# regsimple2addfp.net
KiCad netlist of a schematic drawn in EAGLE
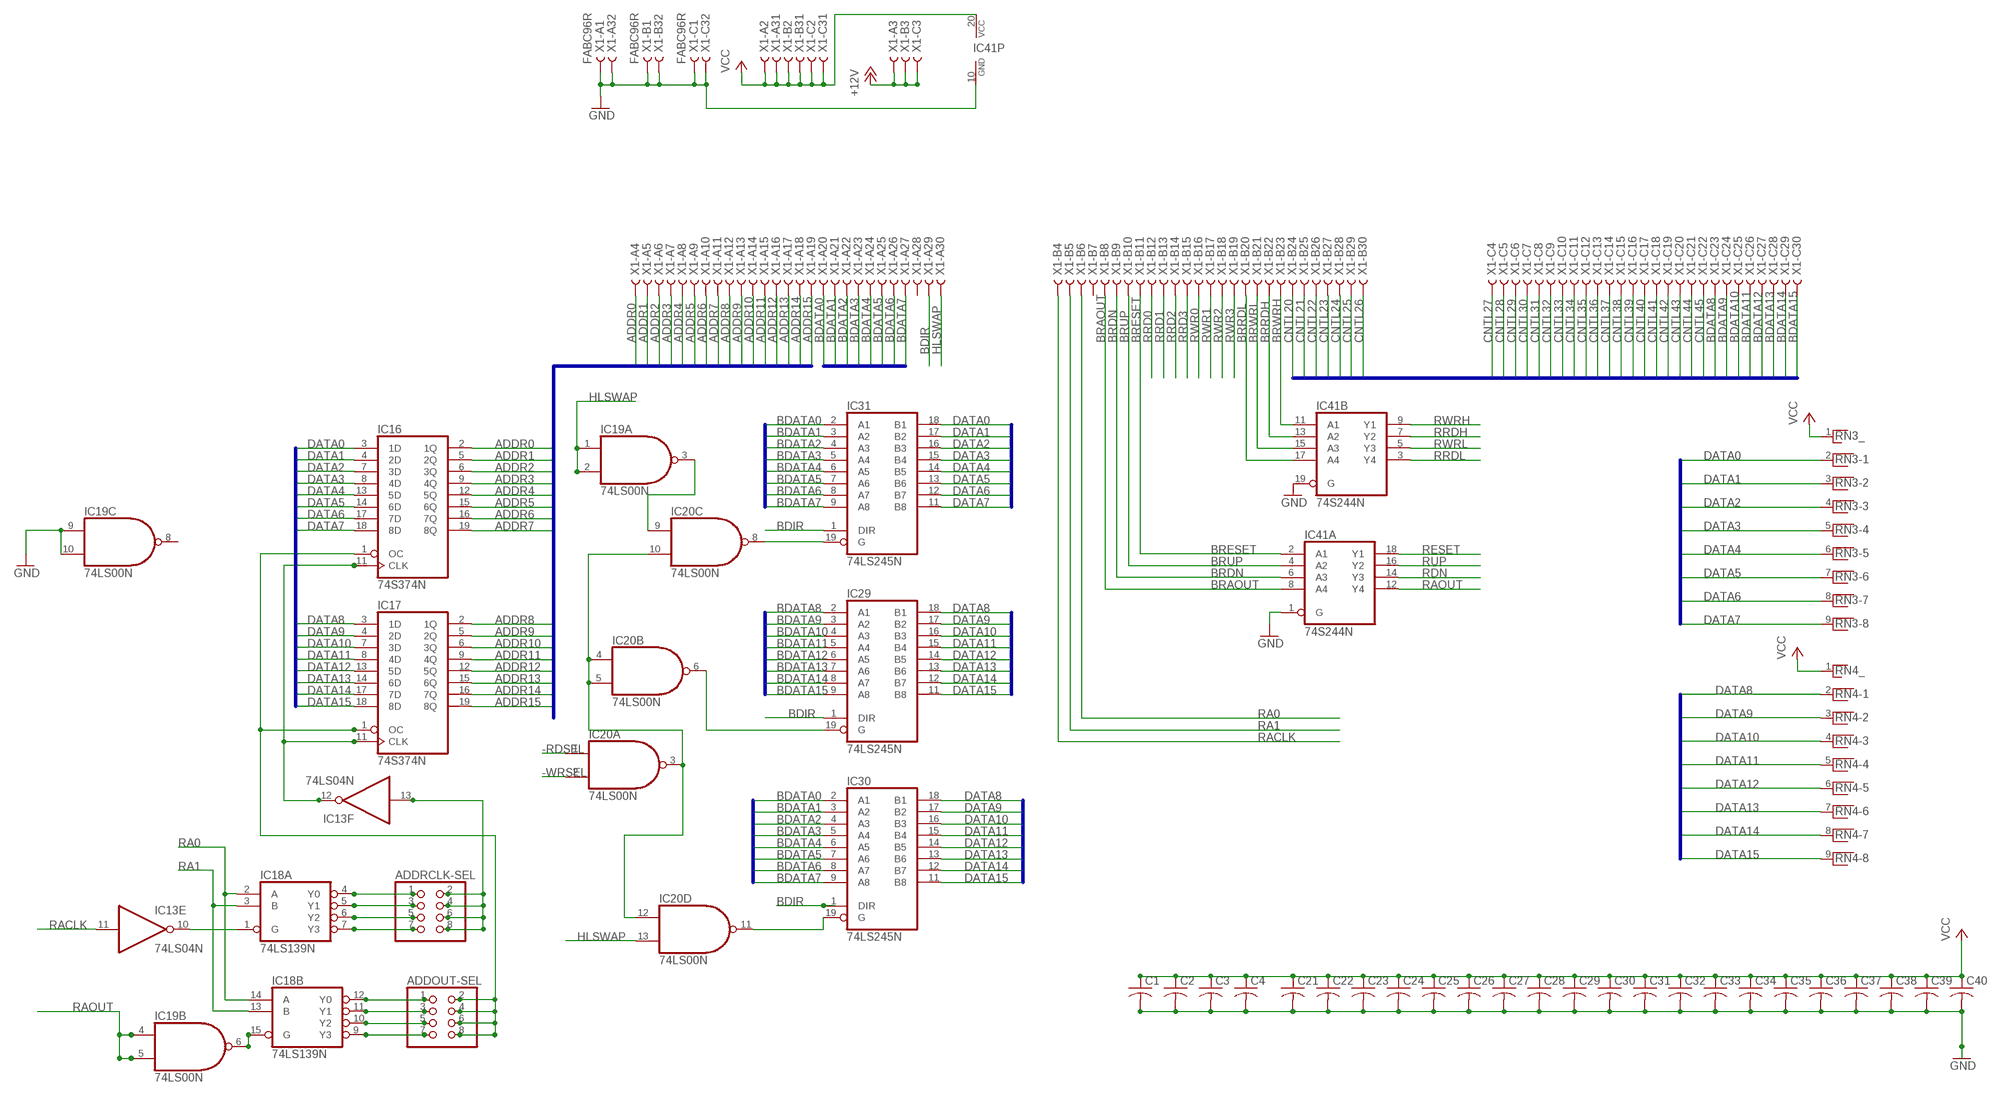
[diagram p0: schematic, sheet 1]
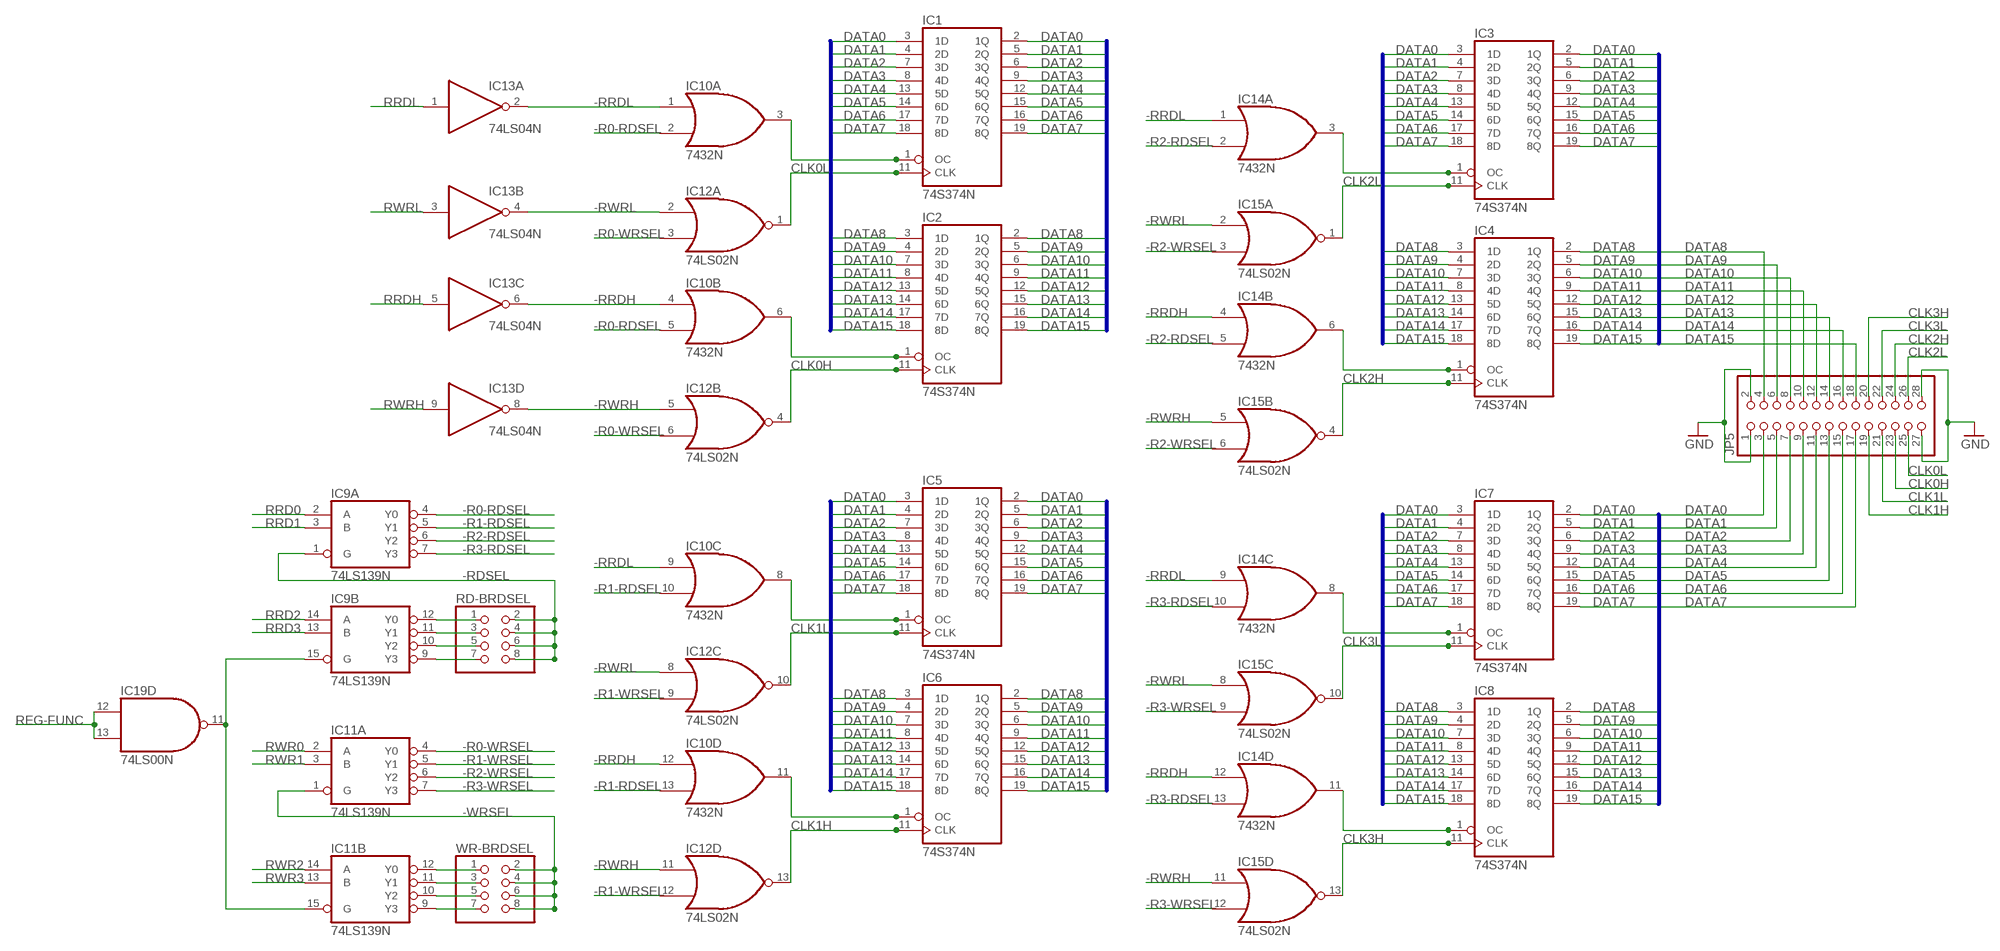
[diagram p1: schematic, sheet 2]

(export (version "E")
  (design (tool "Eeschema 10.0.6"))
  (components
    (comp (ref "IC1")
      (value "74S374N")
      (footprint "eagle-import:DIL20")
      (libsource (lib "eagle-import") (part "74374NS"))
    )
    (comp (ref "IC2")
      (value "74S374N")
      (footprint "eagle-import:DIL20")
      (libsource (lib "eagle-import") (part "74374NS"))
    )
    (comp (ref "IC3")
      (value "74S374N")
      (footprint "eagle-import:DIL20")
      (libsource (lib "eagle-import") (part "74374NS"))
    )
    (comp (ref "IC4")
      (value "74S374N")
      (footprint "eagle-import:DIL20")
      (libsource (lib "eagle-import") (part "74374NS"))
    )
    (comp (ref "IC5")
      (value "74S374N")
      (footprint "eagle-import:DIL20")
      (libsource (lib "eagle-import") (part "74374NS"))
    )
    (comp (ref "IC6")
      (value "74S374N")
      (footprint "eagle-import:DIL20")
      (libsource (lib "eagle-import") (part "74374NS"))
    )
    (comp (ref "IC7")
      (value "74S374N")
      (footprint "eagle-import:DIL20")
      (libsource (lib "eagle-import") (part "74374NS"))
    )
    (comp (ref "IC8")
      (value "74S374N")
      (footprint "eagle-import:DIL20")
      (libsource (lib "eagle-import") (part "74374NS"))
    )
    (comp (ref "IC9")
      (value "74LS139N")
      (footprint "eagle-import:DIL16")
      (libsource (lib "eagle-import") (part "74139NLS"))
    )
    (comp (ref "IC10")
      (value "7432N")
      (footprint "eagle-import:DIL14")
      (libsource (lib "eagle-import") (part "7432N"))
    )
    (comp (ref "IC11")
      (value "74LS139N")
      (footprint "eagle-import:DIL16")
      (libsource (lib "eagle-import") (part "74139NLS"))
    )
    (comp (ref "IC12")
      (value "74LS02N")
      (footprint "eagle-import:DIL14")
      (libsource (lib "eagle-import") (part "7402NLS"))
    )
    (comp (ref "IC13")
      (value "74LS04N")
      (footprint "eagle-import:DIL14")
      (libsource (lib "eagle-import") (part "7404NLS"))
    )
    (comp (ref "IC14")
      (value "7432N")
      (footprint "eagle-import:DIL14")
      (libsource (lib "eagle-import") (part "7432N"))
    )
    (comp (ref "IC15")
      (value "74LS02N")
      (footprint "eagle-import:DIL14")
      (libsource (lib "eagle-import") (part "7402NLS"))
    )
    (comp (ref "IC19")
      (value "74LS00N")
      (footprint "eagle-import:DIL14")
      (libsource (lib "eagle-import") (part "7400NLS"))
    )
    (comp (ref "JP5")
      (value "PINHD-2X14")
      (footprint "eagle-import:2X14")
      (libsource (lib "eagle-import") (part "PINHD-2X14"))
    )
    (comp (ref "RD-BRDSEL")
      (value "PINHD-2X4")
      (footprint "eagle-import:2X04")
      (libsource (lib "eagle-import") (part "PINHD-2X4"))
    )
    (comp (ref "WR-BRDSEL")
      (value "PINHD-2X4")
      (footprint "eagle-import:2X04")
      (libsource (lib "eagle-import") (part "PINHD-2X4"))
    )
    (comp (ref "ADDOUT-SEL")
      (value "PINHD-2X4")
      (footprint "eagle-import:2X04")
      (libsource (lib "eagle-import") (part "PINHD-2X4"))
    )
    (comp (ref "ADDRCLK-SEL")
      (value "PINHD-2X4")
      (footprint "eagle-import:2X04")
      (libsource (lib "eagle-import") (part "PINHD-2X4"))
    )
    (comp (ref "C1")
      (value "C-US025-040X050")
      (footprint "eagle-import:C025-040X050")
      (libsource (lib "eagle-import") (part "C-US025-040X050"))
    )
    (comp (ref "C2")
      (value "C-US025-040X050")
      (footprint "eagle-import:C025-040X050")
      (libsource (lib "eagle-import") (part "C-US025-040X050"))
    )
    (comp (ref "C3")
      (value "C-US025-040X050")
      (footprint "eagle-import:C025-040X050")
      (libsource (lib "eagle-import") (part "C-US025-040X050"))
    )
    (comp (ref "C4")
      (value "C-US025-040X050")
      (footprint "eagle-import:C025-040X050")
      (libsource (lib "eagle-import") (part "C-US025-040X050"))
    )
    (comp (ref "C21")
      (value "C-US025-040X050")
      (footprint "eagle-import:C025-040X050")
      (libsource (lib "eagle-import") (part "C-US025-040X050"))
    )
    (comp (ref "C22")
      (value "C-US025-040X050")
      (footprint "eagle-import:C025-040X050")
      (libsource (lib "eagle-import") (part "C-US025-040X050"))
    )
    (comp (ref "C23")
      (value "C-US025-040X050")
      (footprint "eagle-import:C025-040X050")
      (libsource (lib "eagle-import") (part "C-US025-040X050"))
    )
    (comp (ref "C24")
      (value "C-US025-040X050")
      (footprint "eagle-import:C025-040X050")
      (libsource (lib "eagle-import") (part "C-US025-040X050"))
    )
    (comp (ref "C25")
      (value "C-US025-040X050")
      (footprint "eagle-import:C025-040X050")
      (libsource (lib "eagle-import") (part "C-US025-040X050"))
    )
    (comp (ref "C26")
      (value "C-US025-040X050")
      (footprint "eagle-import:C025-040X050")
      (libsource (lib "eagle-import") (part "C-US025-040X050"))
    )
    (comp (ref "C27")
      (value "C-US025-040X050")
      (footprint "eagle-import:C025-040X050")
      (libsource (lib "eagle-import") (part "C-US025-040X050"))
    )
    (comp (ref "C28")
      (value "C-US025-040X050")
      (footprint "eagle-import:C025-040X050")
      (libsource (lib "eagle-import") (part "C-US025-040X050"))
    )
    (comp (ref "C29")
      (value "C-US025-040X050")
      (footprint "eagle-import:C025-040X050")
      (libsource (lib "eagle-import") (part "C-US025-040X050"))
    )
    (comp (ref "C30")
      (value "C-US025-040X050")
      (footprint "eagle-import:C025-040X050")
      (libsource (lib "eagle-import") (part "C-US025-040X050"))
    )
    (comp (ref "C31")
      (value "C-US025-040X050")
      (footprint "eagle-import:C025-040X050")
      (libsource (lib "eagle-import") (part "C-US025-040X050"))
    )
    (comp (ref "C32")
      (value "C-US025-040X050")
      (footprint "eagle-import:C025-040X050")
      (libsource (lib "eagle-import") (part "C-US025-040X050"))
    )
    (comp (ref "C33")
      (value "C-US025-040X050")
      (footprint "eagle-import:C025-040X050")
      (libsource (lib "eagle-import") (part "C-US025-040X050"))
    )
    (comp (ref "C34")
      (value "C-US025-040X050")
      (footprint "eagle-import:C025-040X050")
      (libsource (lib "eagle-import") (part "C-US025-040X050"))
    )
    (comp (ref "C35")
      (value "C-US025-040X050")
      (footprint "eagle-import:C025-040X050")
      (libsource (lib "eagle-import") (part "C-US025-040X050"))
    )
    (comp (ref "C36")
      (value "C-US025-040X050")
      (footprint "eagle-import:C025-040X050")
      (libsource (lib "eagle-import") (part "C-US025-040X050"))
    )
    (comp (ref "C37")
      (value "C-US025-040X050")
      (footprint "eagle-import:C025-040X050")
      (libsource (lib "eagle-import") (part "C-US025-040X050"))
    )
    (comp (ref "C38")
      (value "C-US025-040X050")
      (footprint "eagle-import:C025-040X050")
      (libsource (lib "eagle-import") (part "C-US025-040X050"))
    )
    (comp (ref "C39")
      (value "C-US025-040X050")
      (footprint "eagle-import:C025-040X050")
      (libsource (lib "eagle-import") (part "C-US025-040X050"))
    )
    (comp (ref "C40")
      (value "C-US025-040X050")
      (footprint "eagle-import:C025-040X050")
      (libsource (lib "eagle-import") (part "C-US025-040X050"))
    )
    (comp (ref "IC16")
      (value "74S374N")
      (footprint "eagle-import:DIL20")
      (libsource (lib "eagle-import") (part "74374NS"))
    )
    (comp (ref "IC17")
      (value "74S374N")
      (footprint "eagle-import:DIL20")
      (libsource (lib "eagle-import") (part "74374NS"))
    )
    (comp (ref "IC18")
      (value "74LS139N")
      (footprint "eagle-import:DIL16")
      (libsource (lib "eagle-import") (part "74139NLS"))
    )
    (comp (ref "IC20")
      (value "74LS00N")
      (footprint "eagle-import:DIL14")
      (libsource (lib "eagle-import") (part "7400NLS"))
    )
    (comp (ref "IC29")
      (value "74LS245N")
      (footprint "eagle-import:DIL20")
      (libsource (lib "eagle-import") (part "74245NLS"))
    )
    (comp (ref "IC30")
      (value "74LS245N")
      (footprint "eagle-import:DIL20")
      (libsource (lib "eagle-import") (part "74245NLS"))
    )
    (comp (ref "IC31")
      (value "74LS245N")
      (footprint "eagle-import:DIL20")
      (libsource (lib "eagle-import") (part "74245NLS"))
    )
    (comp (ref "IC41")
      (value "74S244N")
      (footprint "eagle-import:DIL20")
      (libsource (lib "eagle-import") (part "74244NS"))
    )
    (comp (ref "RN3")
      (value "RNX8")
      (footprint "eagle-import:RN-9")
      (libsource (lib "eagle-import") (part "RNX8"))
    )
    (comp (ref "RN4")
      (value "RNX8")
      (footprint "eagle-import:RN-9")
      (libsource (lib "eagle-import") (part "RNX8"))
    )
    (comp (ref "X1")
      (value "FABC96R")
      (footprint "eagle-import:FABC96R")
      (libsource (lib "eagle-import") (part "FABC96R"))
    )
  )
  (nets
    (net (code "1") (name "+12V") (class "Default")
      (node (ref "X1") (pin "A3") (pinfunction "B_A3") (pintype "passive"))
      (node (ref "X1") (pin "B3") (pinfunction "B_B3") (pintype "passive"))
      (node (ref "X1") (pin "C3") (pinfunction "B_C3") (pintype "passive"))
    )
    (net (code "2") (name "-R0-RDSEL") (class "Default")
      (node (ref "IC10") (pin "2") (pinfunction "I1_2") (pintype "input"))
      (node (ref "IC10") (pin "5") (pinfunction "I1_5") (pintype "input"))
      (node (ref "IC9") (pin "4") (pinfunction "Y0_4") (pintype "output"))
    )
    (net (code "3") (name "-R0-WRSEL") (class "Default")
      (node (ref "IC11") (pin "4") (pinfunction "Y0_4") (pintype "output"))
      (node (ref "IC12") (pin "3") (pinfunction "I1_3") (pintype "input"))
      (node (ref "IC12") (pin "6") (pinfunction "I1_6") (pintype "input"))
    )
    (net (code "4") (name "-R1-RDSEL") (class "Default")
      (node (ref "IC10") (pin "10") (pinfunction "I1_10") (pintype "input"))
      (node (ref "IC10") (pin "13") (pinfunction "I1_13") (pintype "input"))
      (node (ref "IC9") (pin "5") (pinfunction "Y1_5") (pintype "output"))
    )
    (net (code "5") (name "-R1-WRSEL") (class "Default")
      (node (ref "IC11") (pin "5") (pinfunction "Y1_5") (pintype "output"))
      (node (ref "IC12") (pin "12") (pinfunction "I1_12") (pintype "input"))
      (node (ref "IC12") (pin "9") (pinfunction "I1_9") (pintype "input"))
    )
    (net (code "6") (name "-R2-RDSEL") (class "Default")
      (node (ref "IC14") (pin "2") (pinfunction "I1_2") (pintype "input"))
      (node (ref "IC14") (pin "5") (pinfunction "I1_5") (pintype "input"))
      (node (ref "IC9") (pin "6") (pinfunction "Y2_6") (pintype "output"))
    )
    (net (code "7") (name "-R2-WRSEL") (class "Default")
      (node (ref "IC11") (pin "6") (pinfunction "Y2_6") (pintype "output"))
      (node (ref "IC15") (pin "3") (pinfunction "I1_3") (pintype "input"))
      (node (ref "IC15") (pin "6") (pinfunction "I1_6") (pintype "input"))
    )
    (net (code "8") (name "-R3-RDSEL") (class "Default")
      (node (ref "IC14") (pin "10") (pinfunction "I1_10") (pintype "input"))
      (node (ref "IC14") (pin "13") (pinfunction "I1_13") (pintype "input"))
      (node (ref "IC9") (pin "7") (pinfunction "Y3_7") (pintype "output"))
    )
    (net (code "9") (name "-R3-WRSEL") (class "Default")
      (node (ref "IC11") (pin "7") (pinfunction "Y3_7") (pintype "output"))
      (node (ref "IC15") (pin "12") (pinfunction "I1_12") (pintype "input"))
      (node (ref "IC15") (pin "9") (pinfunction "I1_9") (pintype "input"))
    )
    (net (code "10") (name "-RDSEL") (class "Default")
      (node (ref "IC20") (pin "1") (pinfunction "I0_1") (pintype "input"))
      (node (ref "IC9") (pin "1") (pinfunction "G_1") (pintype "input"))
      (node (ref "RD-BRDSEL") (pin "2") (pinfunction "2_2") (pintype "passive"))
      (node (ref "RD-BRDSEL") (pin "4") (pinfunction "4_4") (pintype "passive"))
      (node (ref "RD-BRDSEL") (pin "6") (pinfunction "6_6") (pintype "passive"))
      (node (ref "RD-BRDSEL") (pin "8") (pinfunction "8_8") (pintype "passive"))
    )
    (net (code "11") (name "-RRDH") (class "Default")
      (node (ref "IC10") (pin "12") (pinfunction "I0_12") (pintype "input"))
      (node (ref "IC10") (pin "4") (pinfunction "I0_4") (pintype "input"))
      (node (ref "IC13") (pin "6") (pinfunction "O_6") (pintype "output"))
      (node (ref "IC14") (pin "12") (pinfunction "I0_12") (pintype "input"))
      (node (ref "IC14") (pin "4") (pinfunction "I0_4") (pintype "input"))
    )
    (net (code "12") (name "-RRDL") (class "Default")
      (node (ref "IC10") (pin "1") (pinfunction "I0_1") (pintype "input"))
      (node (ref "IC10") (pin "9") (pinfunction "I0_9") (pintype "input"))
      (node (ref "IC13") (pin "2") (pinfunction "O_2") (pintype "output"))
      (node (ref "IC14") (pin "1") (pinfunction "I0_1") (pintype "input"))
      (node (ref "IC14") (pin "9") (pinfunction "I0_9") (pintype "input"))
    )
    (net (code "13") (name "-RWRH") (class "Default")
      (node (ref "IC12") (pin "11") (pinfunction "I0_11") (pintype "input"))
      (node (ref "IC12") (pin "5") (pinfunction "I0_5") (pintype "input"))
      (node (ref "IC13") (pin "8") (pinfunction "O_8") (pintype "output"))
      (node (ref "IC15") (pin "11") (pinfunction "I0_11") (pintype "input"))
      (node (ref "IC15") (pin "5") (pinfunction "I0_5") (pintype "input"))
    )
    (net (code "14") (name "-RWRL") (class "Default")
      (node (ref "IC12") (pin "2") (pinfunction "I0_2") (pintype "input"))
      (node (ref "IC12") (pin "8") (pinfunction "I0_8") (pintype "input"))
      (node (ref "IC13") (pin "4") (pinfunction "O_4") (pintype "output"))
      (node (ref "IC15") (pin "2") (pinfunction "I0_2") (pintype "input"))
      (node (ref "IC15") (pin "8") (pinfunction "I0_8") (pintype "input"))
    )
    (net (code "15") (name "-WRSEL") (class "Default")
      (node (ref "IC11") (pin "1") (pinfunction "G_1") (pintype "input"))
      (node (ref "IC20") (pin "2") (pinfunction "I1_2") (pintype "input"))
      (node (ref "WR-BRDSEL") (pin "2") (pinfunction "2_2") (pintype "passive"))
      (node (ref "WR-BRDSEL") (pin "4") (pinfunction "4_4") (pintype "passive"))
      (node (ref "WR-BRDSEL") (pin "6") (pinfunction "6_6") (pintype "passive"))
      (node (ref "WR-BRDSEL") (pin "8") (pinfunction "8_8") (pintype "passive"))
    )
    (net (code "16") (name "ADDR0") (class "Default")
      (node (ref "IC16") (pin "2") (pinfunction "1Q_2") (pintype "tri_state"))
      (node (ref "X1") (pin "A4") (pinfunction "B_A4") (pintype "passive"))
    )
    (net (code "17") (name "ADDR1") (class "Default")
      (node (ref "IC16") (pin "5") (pinfunction "2Q_5") (pintype "tri_state"))
      (node (ref "X1") (pin "A5") (pinfunction "B_A5") (pintype "passive"))
    )
    (net (code "18") (name "ADDR2") (class "Default")
      (node (ref "IC16") (pin "6") (pinfunction "3Q_6") (pintype "tri_state"))
      (node (ref "X1") (pin "A6") (pinfunction "B_A6") (pintype "passive"))
    )
    (net (code "19") (name "ADDR3") (class "Default")
      (node (ref "IC16") (pin "9") (pinfunction "4Q_9") (pintype "tri_state"))
      (node (ref "X1") (pin "A7") (pinfunction "B_A7") (pintype "passive"))
    )
    (net (code "20") (name "ADDR4") (class "Default")
      (node (ref "IC16") (pin "12") (pinfunction "5Q_12") (pintype "tri_state"))
      (node (ref "X1") (pin "A8") (pinfunction "B_A8") (pintype "passive"))
    )
    (net (code "21") (name "ADDR5") (class "Default")
      (node (ref "IC16") (pin "15") (pinfunction "6Q_15") (pintype "tri_state"))
      (node (ref "X1") (pin "A9") (pinfunction "B_A9") (pintype "passive"))
    )
    (net (code "22") (name "ADDR6") (class "Default")
      (node (ref "IC16") (pin "16") (pinfunction "7Q_16") (pintype "tri_state"))
      (node (ref "X1") (pin "A10") (pinfunction "B_A10") (pintype "passive"))
    )
    (net (code "23") (name "ADDR7") (class "Default")
      (node (ref "IC16") (pin "19") (pinfunction "8Q_19") (pintype "tri_state"))
      (node (ref "X1") (pin "A11") (pinfunction "B_A11") (pintype "passive"))
    )
    (net (code "24") (name "ADDR8") (class "Default")
      (node (ref "IC17") (pin "2") (pinfunction "1Q_2") (pintype "tri_state"))
      (node (ref "X1") (pin "A12") (pinfunction "B_A12") (pintype "passive"))
    )
    (net (code "25") (name "ADDR9") (class "Default")
      (node (ref "IC17") (pin "5") (pinfunction "2Q_5") (pintype "tri_state"))
      (node (ref "X1") (pin "A13") (pinfunction "B_A13") (pintype "passive"))
    )
    (net (code "26") (name "ADDR10") (class "Default")
      (node (ref "IC17") (pin "6") (pinfunction "3Q_6") (pintype "tri_state"))
      (node (ref "X1") (pin "A14") (pinfunction "B_A14") (pintype "passive"))
    )
    (net (code "27") (name "ADDR11") (class "Default")
      (node (ref "IC17") (pin "9") (pinfunction "4Q_9") (pintype "tri_state"))
      (node (ref "X1") (pin "A15") (pinfunction "B_A15") (pintype "passive"))
    )
    (net (code "28") (name "ADDR12") (class "Default")
      (node (ref "IC17") (pin "12") (pinfunction "5Q_12") (pintype "tri_state"))
      (node (ref "X1") (pin "A16") (pinfunction "B_A16") (pintype "passive"))
    )
    (net (code "29") (name "ADDR13") (class "Default")
      (node (ref "IC17") (pin "15") (pinfunction "6Q_15") (pintype "tri_state"))
      (node (ref "X1") (pin "A17") (pinfunction "B_A17") (pintype "passive"))
    )
    (net (code "30") (name "ADDR14") (class "Default")
      (node (ref "IC17") (pin "16") (pinfunction "7Q_16") (pintype "tri_state"))
      (node (ref "X1") (pin "A18") (pinfunction "B_A18") (pintype "passive"))
    )
    (net (code "31") (name "ADDR15") (class "Default")
      (node (ref "IC17") (pin "19") (pinfunction "8Q_19") (pintype "tri_state"))
      (node (ref "X1") (pin "A19") (pinfunction "B_A19") (pintype "passive"))
    )
    (net (code "32") (name "BDATA0") (class "Default")
      (node (ref "IC30") (pin "2") (pinfunction "A1_2") (pintype "bidirectional"))
      (node (ref "IC31") (pin "2") (pinfunction "A1_2") (pintype "bidirectional"))
      (node (ref "X1") (pin "A20") (pinfunction "B_A20") (pintype "passive"))
    )
    (net (code "33") (name "BDATA1") (class "Default")
      (node (ref "IC30") (pin "3") (pinfunction "A2_3") (pintype "bidirectional"))
      (node (ref "IC31") (pin "3") (pinfunction "A2_3") (pintype "bidirectional"))
      (node (ref "X1") (pin "A21") (pinfunction "B_A21") (pintype "passive"))
    )
    (net (code "34") (name "BDATA2") (class "Default")
      (node (ref "IC30") (pin "4") (pinfunction "A3_4") (pintype "bidirectional"))
      (node (ref "IC31") (pin "4") (pinfunction "A3_4") (pintype "bidirectional"))
      (node (ref "X1") (pin "A22") (pinfunction "B_A22") (pintype "passive"))
    )
    (net (code "35") (name "BDATA3") (class "Default")
      (node (ref "IC30") (pin "5") (pinfunction "A4_5") (pintype "bidirectional"))
      (node (ref "IC31") (pin "5") (pinfunction "A4_5") (pintype "bidirectional"))
      (node (ref "X1") (pin "A23") (pinfunction "B_A23") (pintype "passive"))
    )
    (net (code "36") (name "BDATA4") (class "Default")
      (node (ref "IC30") (pin "6") (pinfunction "A5_6") (pintype "bidirectional"))
      (node (ref "IC31") (pin "6") (pinfunction "A5_6") (pintype "bidirectional"))
      (node (ref "X1") (pin "A24") (pinfunction "B_A24") (pintype "passive"))
    )
    (net (code "37") (name "BDATA5") (class "Default")
      (node (ref "IC30") (pin "7") (pinfunction "A6_7") (pintype "bidirectional"))
      (node (ref "IC31") (pin "7") (pinfunction "A6_7") (pintype "bidirectional"))
      (node (ref "X1") (pin "A25") (pinfunction "B_A25") (pintype "passive"))
    )
    (net (code "38") (name "BDATA6") (class "Default")
      (node (ref "IC30") (pin "8") (pinfunction "A7_8") (pintype "bidirectional"))
      (node (ref "IC31") (pin "8") (pinfunction "A7_8") (pintype "bidirectional"))
      (node (ref "X1") (pin "A26") (pinfunction "B_A26") (pintype "passive"))
    )
    (net (code "39") (name "BDATA7") (class "Default")
      (node (ref "IC30") (pin "9") (pinfunction "A8_9") (pintype "bidirectional"))
      (node (ref "IC31") (pin "9") (pinfunction "A8_9") (pintype "bidirectional"))
      (node (ref "X1") (pin "A27") (pinfunction "B_A27") (pintype "passive"))
    )
    (net (code "40") (name "BDATA8") (class "Default")
      (node (ref "IC29") (pin "2") (pinfunction "A1_2") (pintype "bidirectional"))
      (node (ref "X1") (pin "C23") (pinfunction "B_C23") (pintype "passive"))
    )
    (net (code "41") (name "BDATA9") (class "Default")
      (node (ref "IC29") (pin "3") (pinfunction "A2_3") (pintype "bidirectional"))
      (node (ref "X1") (pin "C24") (pinfunction "B_C24") (pintype "passive"))
    )
    (net (code "42") (name "BDATA10") (class "Default")
      (node (ref "IC29") (pin "4") (pinfunction "A3_4") (pintype "bidirectional"))
      (node (ref "X1") (pin "C25") (pinfunction "B_C25") (pintype "passive"))
    )
    (net (code "43") (name "BDATA11") (class "Default")
      (node (ref "IC29") (pin "5") (pinfunction "A4_5") (pintype "bidirectional"))
      (node (ref "X1") (pin "C26") (pinfunction "B_C26") (pintype "passive"))
    )
    (net (code "44") (name "BDATA12") (class "Default")
      (node (ref "IC29") (pin "6") (pinfunction "A5_6") (pintype "bidirectional"))
      (node (ref "X1") (pin "C27") (pinfunction "B_C27") (pintype "passive"))
    )
    (net (code "45") (name "BDATA13") (class "Default")
      (node (ref "IC29") (pin "7") (pinfunction "A6_7") (pintype "bidirectional"))
      (node (ref "X1") (pin "C28") (pinfunction "B_C28") (pintype "passive"))
    )
    (net (code "46") (name "BDATA14") (class "Default")
      (node (ref "IC29") (pin "8") (pinfunction "A7_8") (pintype "bidirectional"))
      (node (ref "X1") (pin "C29") (pinfunction "B_C29") (pintype "passive"))
    )
    (net (code "47") (name "BDATA15") (class "Default")
      (node (ref "IC29") (pin "9") (pinfunction "A8_9") (pintype "bidirectional"))
      (node (ref "X1") (pin "C30") (pinfunction "B_C30") (pintype "passive"))
    )
    (net (code "48") (name "BDIR") (class "Default")
      (node (ref "IC29") (pin "1") (pinfunction "DIR_1") (pintype "input"))
      (node (ref "IC30") (pin "1") (pinfunction "DIR_1") (pintype "input"))
      (node (ref "IC31") (pin "1") (pinfunction "DIR_1") (pintype "input"))
      (node (ref "X1") (pin "A29") (pinfunction "B_A29") (pintype "passive"))
    )
    (net (code "49") (name "BRAOUT") (class "Default")
      (node (ref "IC41") (pin "8") (pinfunction "A4_8") (pintype "input"))
      (node (ref "X1") (pin "B8") (pinfunction "B_B8") (pintype "passive"))
    )
    (net (code "50") (name "BRDN") (class "Default")
      (node (ref "IC41") (pin "6") (pinfunction "A3_6") (pintype "input"))
      (node (ref "X1") (pin "B9") (pinfunction "B_B9") (pintype "passive"))
    )
    (net (code "51") (name "BRESET") (class "Default")
      (node (ref "IC41") (pin "2") (pinfunction "A1_2") (pintype "input"))
      (node (ref "X1") (pin "B11") (pinfunction "B_B11") (pintype "passive"))
    )
    (net (code "52") (name "BRRDH") (class "Default")
      (node (ref "IC41") (pin "13") (pinfunction "A2_13") (pintype "input"))
      (node (ref "X1") (pin "B22") (pinfunction "B_B22") (pintype "passive"))
    )
    (net (code "53") (name "BRRDL") (class "Default")
      (node (ref "IC41") (pin "17") (pinfunction "A4_17") (pintype "input"))
      (node (ref "X1") (pin "B20") (pinfunction "B_B20") (pintype "passive"))
    )
    (net (code "54") (name "BRUP") (class "Default")
      (node (ref "IC41") (pin "4") (pinfunction "A2_4") (pintype "input"))
      (node (ref "X1") (pin "B10") (pinfunction "B_B10") (pintype "passive"))
    )
    (net (code "55") (name "BRWRH") (class "Default")
      (node (ref "IC41") (pin "11") (pinfunction "A1_11") (pintype "input"))
      (node (ref "X1") (pin "B23") (pinfunction "B_B23") (pintype "passive"))
    )
    (net (code "56") (name "BRWRL") (class "Default")
      (node (ref "IC41") (pin "15") (pinfunction "A3_15") (pintype "input"))
      (node (ref "X1") (pin "B21") (pinfunction "B_B21") (pintype "passive"))
    )
    (net (code "57") (name "CLK0H") (class "Default")
      (node (ref "IC12") (pin "4") (pinfunction "O_4") (pintype "output"))
      (node (ref "IC2") (pin "11") (pinfunction "CLK_11") (pintype "input"))
      (node (ref "JP5") (pin "23") (pinfunction "23_23") (pintype "passive"))
    )
    (net (code "58") (name "CLK0L") (class "Default")
      (node (ref "IC1") (pin "11") (pinfunction "CLK_11") (pintype "input"))
      (node (ref "IC12") (pin "1") (pinfunction "O_1") (pintype "output"))
      (node (ref "JP5") (pin "25") (pinfunction "25_25") (pintype "passive"))
    )
    (net (code "59") (name "CLK1H") (class "Default")
      (node (ref "IC12") (pin "13") (pinfunction "O_13") (pintype "output"))
      (node (ref "IC6") (pin "11") (pinfunction "CLK_11") (pintype "input"))
      (node (ref "JP5") (pin "19") (pinfunction "19_19") (pintype "passive"))
    )
    (net (code "60") (name "CLK1L") (class "Default")
      (node (ref "IC12") (pin "10") (pinfunction "O_10") (pintype "output"))
      (node (ref "IC5") (pin "11") (pinfunction "CLK_11") (pintype "input"))
      (node (ref "JP5") (pin "21") (pinfunction "21_21") (pintype "passive"))
    )
    (net (code "61") (name "CLK2H") (class "Default")
      (node (ref "IC15") (pin "4") (pinfunction "O_4") (pintype "output"))
      (node (ref "IC4") (pin "11") (pinfunction "CLK_11") (pintype "input"))
      (node (ref "JP5") (pin "24") (pinfunction "24_24") (pintype "passive"))
    )
    (net (code "62") (name "CLK2L") (class "Default")
      (node (ref "IC15") (pin "1") (pinfunction "O_1") (pintype "output"))
      (node (ref "IC3") (pin "11") (pinfunction "CLK_11") (pintype "input"))
      (node (ref "JP5") (pin "26") (pinfunction "26_26") (pintype "passive"))
    )
    (net (code "63") (name "CLK3H") (class "Default")
      (node (ref "IC15") (pin "13") (pinfunction "O_13") (pintype "output"))
      (node (ref "IC8") (pin "11") (pinfunction "CLK_11") (pintype "input"))
      (node (ref "JP5") (pin "20") (pinfunction "20_20") (pintype "passive"))
    )
    (net (code "64") (name "CLK3L") (class "Default")
      (node (ref "IC15") (pin "10") (pinfunction "O_10") (pintype "output"))
      (node (ref "IC7") (pin "11") (pinfunction "CLK_11") (pintype "input"))
      (node (ref "JP5") (pin "22") (pinfunction "22_22") (pintype "passive"))
    )
    (net (code "65") (name "CNTL20") (class "Default")
      (node (ref "X1") (pin "B24") (pinfunction "B_B24") (pintype "passive"))
    )
    (net (code "66") (name "CNTL21") (class "Default")
      (node (ref "X1") (pin "B25") (pinfunction "B_B25") (pintype "passive"))
    )
    (net (code "67") (name "CNTL22") (class "Default")
      (node (ref "X1") (pin "B26") (pinfunction "B_B26") (pintype "passive"))
    )
    (net (code "68") (name "CNTL23") (class "Default")
      (node (ref "X1") (pin "B27") (pinfunction "B_B27") (pintype "passive"))
    )
    (net (code "69") (name "CNTL24") (class "Default")
      (node (ref "X1") (pin "B28") (pinfunction "B_B28") (pintype "passive"))
    )
    (net (code "70") (name "CNTL25") (class "Default")
      (node (ref "X1") (pin "B29") (pinfunction "B_B29") (pintype "passive"))
    )
    (net (code "71") (name "CNTL26") (class "Default")
      (node (ref "X1") (pin "B30") (pinfunction "B_B30") (pintype "passive"))
    )
    (net (code "72") (name "CNTL27") (class "Default")
      (node (ref "X1") (pin "C4") (pinfunction "B_C4") (pintype "passive"))
    )
    (net (code "73") (name "CNTL28") (class "Default")
      (node (ref "X1") (pin "C5") (pinfunction "B_C5") (pintype "passive"))
    )
    (net (code "74") (name "CNTL29") (class "Default")
      (node (ref "X1") (pin "C6") (pinfunction "B_C6") (pintype "passive"))
    )
    (net (code "75") (name "CNTL30") (class "Default")
      (node (ref "X1") (pin "C7") (pinfunction "B_C7") (pintype "passive"))
    )
    (net (code "76") (name "CNTL31") (class "Default")
      (node (ref "X1") (pin "C8") (pinfunction "B_C8") (pintype "passive"))
    )
    (net (code "77") (name "CNTL32") (class "Default")
      (node (ref "X1") (pin "C9") (pinfunction "B_C9") (pintype "passive"))
    )
    (net (code "78") (name "CNTL33") (class "Default")
      (node (ref "X1") (pin "C10") (pinfunction "B_C10") (pintype "passive"))
    )
    (net (code "79") (name "CNTL34") (class "Default")
      (node (ref "X1") (pin "C11") (pinfunction "B_C11") (pintype "passive"))
    )
    (net (code "80") (name "CNTL35") (class "Default")
      (node (ref "X1") (pin "C12") (pinfunction "B_C12") (pintype "passive"))
    )
    (net (code "81") (name "CNTL36") (class "Default")
      (node (ref "X1") (pin "C13") (pinfunction "B_C13") (pintype "passive"))
    )
    (net (code "82") (name "CNTL37") (class "Default")
      (node (ref "X1") (pin "C14") (pinfunction "B_C14") (pintype "passive"))
    )
    (net (code "83") (name "CNTL38") (class "Default")
      (node (ref "X1") (pin "C15") (pinfunction "B_C15") (pintype "passive"))
    )
    (net (code "84") (name "CNTL39") (class "Default")
      (node (ref "X1") (pin "C16") (pinfunction "B_C16") (pintype "passive"))
    )
    (net (code "85") (name "CNTL40") (class "Default")
      (node (ref "X1") (pin "C17") (pinfunction "B_C17") (pintype "passive"))
    )
    (net (code "86") (name "CNTL41") (class "Default")
      (node (ref "X1") (pin "C18") (pinfunction "B_C18") (pintype "passive"))
    )
    (net (code "87") (name "CNTL42") (class "Default")
      (node (ref "X1") (pin "C19") (pinfunction "B_C19") (pintype "passive"))
    )
    (net (code "88") (name "CNTL43") (class "Default")
      (node (ref "X1") (pin "C20") (pinfunction "B_C20") (pintype "passive"))
    )
    (net (code "89") (name "CNTL44") (class "Default")
      (node (ref "X1") (pin "C21") (pinfunction "B_C21") (pintype "passive"))
    )
    (net (code "90") (name "CNTL45") (class "Default")
      (node (ref "X1") (pin "C22") (pinfunction "B_C22") (pintype "passive"))
    )
    (net (code "91") (name "DATA0") (class "Default")
      (node (ref "IC1") (pin "2") (pinfunction "1Q_2") (pintype "tri_state"))
      (node (ref "IC1") (pin "3") (pinfunction "1D_3") (pintype "input"))
      (node (ref "IC16") (pin "3") (pinfunction "1D_3") (pintype "input"))
      (node (ref "IC3") (pin "2") (pinfunction "1Q_2") (pintype "tri_state"))
      (node (ref "IC3") (pin "3") (pinfunction "1D_3") (pintype "input"))
      (node (ref "IC31") (pin "18") (pinfunction "B1_18") (pintype "bidirectional"))
      (node (ref "IC5") (pin "2") (pinfunction "1Q_2") (pintype "tri_state"))
      (node (ref "IC5") (pin "3") (pinfunction "1D_3") (pintype "input"))
      (node (ref "IC7") (pin "2") (pinfunction "1Q_2") (pintype "tri_state"))
      (node (ref "IC7") (pin "3") (pinfunction "1D_3") (pintype "input"))
      (node (ref "JP5") (pin "3") (pinfunction "3_3") (pintype "passive"))
      (node (ref "RN3") (pin "2") (pinfunction "1_2") (pintype "passive"))
    )
    (net (code "92") (name "DATA1") (class "Default")
      (node (ref "IC1") (pin "4") (pinfunction "2D_4") (pintype "input"))
      (node (ref "IC1") (pin "5") (pinfunction "2Q_5") (pintype "tri_state"))
      (node (ref "IC16") (pin "4") (pinfunction "2D_4") (pintype "input"))
      (node (ref "IC3") (pin "4") (pinfunction "2D_4") (pintype "input"))
      (node (ref "IC3") (pin "5") (pinfunction "2Q_5") (pintype "tri_state"))
      (node (ref "IC31") (pin "17") (pinfunction "B2_17") (pintype "bidirectional"))
      (node (ref "IC5") (pin "4") (pinfunction "2D_4") (pintype "input"))
      (node (ref "IC5") (pin "5") (pinfunction "2Q_5") (pintype "tri_state"))
      (node (ref "IC7") (pin "4") (pinfunction "2D_4") (pintype "input"))
      (node (ref "IC7") (pin "5") (pinfunction "2Q_5") (pintype "tri_state"))
      (node (ref "JP5") (pin "5") (pinfunction "5_5") (pintype "passive"))
      (node (ref "RN3") (pin "3") (pinfunction "1_3") (pintype "passive"))
    )
    (net (code "93") (name "DATA2") (class "Default")
      (node (ref "IC1") (pin "6") (pinfunction "3Q_6") (pintype "tri_state"))
      (node (ref "IC1") (pin "7") (pinfunction "3D_7") (pintype "input"))
      (node (ref "IC16") (pin "7") (pinfunction "3D_7") (pintype "input"))
      (node (ref "IC3") (pin "6") (pinfunction "3Q_6") (pintype "tri_state"))
      (node (ref "IC3") (pin "7") (pinfunction "3D_7") (pintype "input"))
      (node (ref "IC31") (pin "16") (pinfunction "B3_16") (pintype "bidirectional"))
      (node (ref "IC5") (pin "6") (pinfunction "3Q_6") (pintype "tri_state"))
      (node (ref "IC5") (pin "7") (pinfunction "3D_7") (pintype "input"))
      (node (ref "IC7") (pin "6") (pinfunction "3Q_6") (pintype "tri_state"))
      (node (ref "IC7") (pin "7") (pinfunction "3D_7") (pintype "input"))
      (node (ref "JP5") (pin "7") (pinfunction "7_7") (pintype "passive"))
      (node (ref "RN3") (pin "4") (pinfunction "1_4") (pintype "passive"))
    )
    (net (code "94") (name "DATA3") (class "Default")
      (node (ref "IC1") (pin "8") (pinfunction "4D_8") (pintype "input"))
      (node (ref "IC1") (pin "9") (pinfunction "4Q_9") (pintype "tri_state"))
      (node (ref "IC16") (pin "8") (pinfunction "4D_8") (pintype "input"))
      (node (ref "IC3") (pin "8") (pinfunction "4D_8") (pintype "input"))
      (node (ref "IC3") (pin "9") (pinfunction "4Q_9") (pintype "tri_state"))
      (node (ref "IC31") (pin "15") (pinfunction "B4_15") (pintype "bidirectional"))
      (node (ref "IC5") (pin "8") (pinfunction "4D_8") (pintype "input"))
      (node (ref "IC5") (pin "9") (pinfunction "4Q_9") (pintype "tri_state"))
      (node (ref "IC7") (pin "8") (pinfunction "4D_8") (pintype "input"))
      (node (ref "IC7") (pin "9") (pinfunction "4Q_9") (pintype "tri_state"))
      (node (ref "JP5") (pin "9") (pinfunction "9_9") (pintype "passive"))
      (node (ref "RN3") (pin "5") (pinfunction "1_5") (pintype "passive"))
    )
    (net (code "95") (name "DATA4") (class "Default")
      (node (ref "IC1") (pin "12") (pinfunction "5Q_12") (pintype "tri_state"))
      (node (ref "IC1") (pin "13") (pinfunction "5D_13") (pintype "input"))
      (node (ref "IC16") (pin "13") (pinfunction "5D_13") (pintype "input"))
      (node (ref "IC3") (pin "12") (pinfunction "5Q_12") (pintype "tri_state"))
      (node (ref "IC3") (pin "13") (pinfunction "5D_13") (pintype "input"))
      (node (ref "IC31") (pin "14") (pinfunction "B5_14") (pintype "bidirectional"))
      (node (ref "IC5") (pin "12") (pinfunction "5Q_12") (pintype "tri_state"))
      (node (ref "IC5") (pin "13") (pinfunction "5D_13") (pintype "input"))
      (node (ref "IC7") (pin "12") (pinfunction "5Q_12") (pintype "tri_state"))
      (node (ref "IC7") (pin "13") (pinfunction "5D_13") (pintype "input"))
      (node (ref "JP5") (pin "11") (pinfunction "11_11") (pintype "passive"))
      (node (ref "RN3") (pin "6") (pinfunction "1_6") (pintype "passive"))
    )
    (net (code "96") (name "DATA5") (class "Default")
      (node (ref "IC1") (pin "14") (pinfunction "6D_14") (pintype "input"))
      (node (ref "IC1") (pin "15") (pinfunction "6Q_15") (pintype "tri_state"))
      (node (ref "IC16") (pin "14") (pinfunction "6D_14") (pintype "input"))
      (node (ref "IC3") (pin "14") (pinfunction "6D_14") (pintype "input"))
      (node (ref "IC3") (pin "15") (pinfunction "6Q_15") (pintype "tri_state"))
      (node (ref "IC31") (pin "13") (pinfunction "B6_13") (pintype "bidirectional"))
      (node (ref "IC5") (pin "14") (pinfunction "6D_14") (pintype "input"))
      (node (ref "IC5") (pin "15") (pinfunction "6Q_15") (pintype "tri_state"))
      (node (ref "IC7") (pin "14") (pinfunction "6D_14") (pintype "input"))
      (node (ref "IC7") (pin "15") (pinfunction "6Q_15") (pintype "tri_state"))
      (node (ref "JP5") (pin "13") (pinfunction "13_13") (pintype "passive"))
      (node (ref "RN3") (pin "7") (pinfunction "1_7") (pintype "passive"))
    )
    (net (code "97") (name "DATA6") (class "Default")
      (node (ref "IC1") (pin "16") (pinfunction "7Q_16") (pintype "tri_state"))
      (node (ref "IC1") (pin "17") (pinfunction "7D_17") (pintype "input"))
      (node (ref "IC16") (pin "17") (pinfunction "7D_17") (pintype "input"))
      (node (ref "IC3") (pin "16") (pinfunction "7Q_16") (pintype "tri_state"))
      (node (ref "IC3") (pin "17") (pinfunction "7D_17") (pintype "input"))
      (node (ref "IC31") (pin "12") (pinfunction "B7_12") (pintype "bidirectional"))
      (node (ref "IC5") (pin "16") (pinfunction "7Q_16") (pintype "tri_state"))
      (node (ref "IC5") (pin "17") (pinfunction "7D_17") (pintype "input"))
      (node (ref "IC7") (pin "16") (pinfunction "7Q_16") (pintype "tri_state"))
      (node (ref "IC7") (pin "17") (pinfunction "7D_17") (pintype "input"))
      (node (ref "JP5") (pin "15") (pinfunction "15_15") (pintype "passive"))
      (node (ref "RN3") (pin "8") (pinfunction "1_8") (pintype "passive"))
    )
    (net (code "98") (name "DATA7") (class "Default")
      (node (ref "IC1") (pin "18") (pinfunction "8D_18") (pintype "input"))
      (node (ref "IC1") (pin "19") (pinfunction "8Q_19") (pintype "tri_state"))
      (node (ref "IC16") (pin "18") (pinfunction "8D_18") (pintype "input"))
      (node (ref "IC3") (pin "18") (pinfunction "8D_18") (pintype "input"))
      (node (ref "IC3") (pin "19") (pinfunction "8Q_19") (pintype "tri_state"))
      (node (ref "IC31") (pin "11") (pinfunction "B8_11") (pintype "bidirectional"))
      (node (ref "IC5") (pin "18") (pinfunction "8D_18") (pintype "input"))
      (node (ref "IC5") (pin "19") (pinfunction "8Q_19") (pintype "tri_state"))
      (node (ref "IC7") (pin "18") (pinfunction "8D_18") (pintype "input"))
      (node (ref "IC7") (pin "19") (pinfunction "8Q_19") (pintype "tri_state"))
      (node (ref "JP5") (pin "17") (pinfunction "17_17") (pintype "passive"))
      (node (ref "RN3") (pin "9") (pinfunction "1_9") (pintype "passive"))
    )
    (net (code "99") (name "DATA8") (class "Default")
      (node (ref "IC17") (pin "3") (pinfunction "1D_3") (pintype "input"))
      (node (ref "IC2") (pin "2") (pinfunction "1Q_2") (pintype "tri_state"))
      (node (ref "IC2") (pin "3") (pinfunction "1D_3") (pintype "input"))
      (node (ref "IC29") (pin "18") (pinfunction "B1_18") (pintype "bidirectional"))
      (node (ref "IC30") (pin "18") (pinfunction "B1_18") (pintype "bidirectional"))
      (node (ref "IC4") (pin "2") (pinfunction "1Q_2") (pintype "tri_state"))
      (node (ref "IC4") (pin "3") (pinfunction "1D_3") (pintype "input"))
      (node (ref "IC6") (pin "2") (pinfunction "1Q_2") (pintype "tri_state"))
      (node (ref "IC6") (pin "3") (pinfunction "1D_3") (pintype "input"))
      (node (ref "IC8") (pin "2") (pinfunction "1Q_2") (pintype "tri_state"))
      (node (ref "IC8") (pin "3") (pinfunction "1D_3") (pintype "input"))
      (node (ref "JP5") (pin "4") (pinfunction "4_4") (pintype "passive"))
      (node (ref "RN4") (pin "2") (pinfunction "1_2") (pintype "passive"))
    )
    (net (code "100") (name "DATA9") (class "Default")
      (node (ref "IC17") (pin "4") (pinfunction "2D_4") (pintype "input"))
      (node (ref "IC2") (pin "4") (pinfunction "2D_4") (pintype "input"))
      (node (ref "IC2") (pin "5") (pinfunction "2Q_5") (pintype "tri_state"))
      (node (ref "IC29") (pin "17") (pinfunction "B2_17") (pintype "bidirectional"))
      (node (ref "IC30") (pin "17") (pinfunction "B2_17") (pintype "bidirectional"))
      (node (ref "IC4") (pin "4") (pinfunction "2D_4") (pintype "input"))
      (node (ref "IC4") (pin "5") (pinfunction "2Q_5") (pintype "tri_state"))
      (node (ref "IC6") (pin "4") (pinfunction "2D_4") (pintype "input"))
      (node (ref "IC6") (pin "5") (pinfunction "2Q_5") (pintype "tri_state"))
      (node (ref "IC8") (pin "4") (pinfunction "2D_4") (pintype "input"))
      (node (ref "IC8") (pin "5") (pinfunction "2Q_5") (pintype "tri_state"))
      (node (ref "JP5") (pin "6") (pinfunction "6_6") (pintype "passive"))
      (node (ref "RN4") (pin "3") (pinfunction "1_3") (pintype "passive"))
    )
    (net (code "101") (name "DATA10") (class "Default")
      (node (ref "IC17") (pin "7") (pinfunction "3D_7") (pintype "input"))
      (node (ref "IC2") (pin "6") (pinfunction "3Q_6") (pintype "tri_state"))
      (node (ref "IC2") (pin "7") (pinfunction "3D_7") (pintype "input"))
      (node (ref "IC29") (pin "16") (pinfunction "B3_16") (pintype "bidirectional"))
      (node (ref "IC30") (pin "16") (pinfunction "B3_16") (pintype "bidirectional"))
      (node (ref "IC4") (pin "6") (pinfunction "3Q_6") (pintype "tri_state"))
      (node (ref "IC4") (pin "7") (pinfunction "3D_7") (pintype "input"))
      (node (ref "IC6") (pin "6") (pinfunction "3Q_6") (pintype "tri_state"))
      (node (ref "IC6") (pin "7") (pinfunction "3D_7") (pintype "input"))
      (node (ref "IC8") (pin "6") (pinfunction "3Q_6") (pintype "tri_state"))
      (node (ref "IC8") (pin "7") (pinfunction "3D_7") (pintype "input"))
      (node (ref "JP5") (pin "8") (pinfunction "8_8") (pintype "passive"))
      (node (ref "RN4") (pin "4") (pinfunction "1_4") (pintype "passive"))
    )
    (net (code "102") (name "DATA11") (class "Default")
      (node (ref "IC17") (pin "8") (pinfunction "4D_8") (pintype "input"))
      (node (ref "IC2") (pin "8") (pinfunction "4D_8") (pintype "input"))
      (node (ref "IC2") (pin "9") (pinfunction "4Q_9") (pintype "tri_state"))
      (node (ref "IC29") (pin "15") (pinfunction "B4_15") (pintype "bidirectional"))
      (node (ref "IC30") (pin "15") (pinfunction "B4_15") (pintype "bidirectional"))
      (node (ref "IC4") (pin "8") (pinfunction "4D_8") (pintype "input"))
      (node (ref "IC4") (pin "9") (pinfunction "4Q_9") (pintype "tri_state"))
      (node (ref "IC6") (pin "8") (pinfunction "4D_8") (pintype "input"))
      (node (ref "IC6") (pin "9") (pinfunction "4Q_9") (pintype "tri_state"))
      (node (ref "IC8") (pin "8") (pinfunction "4D_8") (pintype "input"))
      (node (ref "IC8") (pin "9") (pinfunction "4Q_9") (pintype "tri_state"))
      (node (ref "JP5") (pin "10") (pinfunction "10_10") (pintype "passive"))
      (node (ref "RN4") (pin "5") (pinfunction "1_5") (pintype "passive"))
    )
    (net (code "103") (name "DATA12") (class "Default")
      (node (ref "IC17") (pin "13") (pinfunction "5D_13") (pintype "input"))
      (node (ref "IC2") (pin "12") (pinfunction "5Q_12") (pintype "tri_state"))
      (node (ref "IC2") (pin "13") (pinfunction "5D_13") (pintype "input"))
      (node (ref "IC29") (pin "14") (pinfunction "B5_14") (pintype "bidirectional"))
      (node (ref "IC30") (pin "14") (pinfunction "B5_14") (pintype "bidirectional"))
      (node (ref "IC4") (pin "12") (pinfunction "5Q_12") (pintype "tri_state"))
      (node (ref "IC4") (pin "13") (pinfunction "5D_13") (pintype "input"))
      (node (ref "IC6") (pin "12") (pinfunction "5Q_12") (pintype "tri_state"))
      (node (ref "IC6") (pin "13") (pinfunction "5D_13") (pintype "input"))
      (node (ref "IC8") (pin "12") (pinfunction "5Q_12") (pintype "tri_state"))
      (node (ref "IC8") (pin "13") (pinfunction "5D_13") (pintype "input"))
      (node (ref "JP5") (pin "12") (pinfunction "12_12") (pintype "passive"))
      (node (ref "RN4") (pin "6") (pinfunction "1_6") (pintype "passive"))
    )
    (net (code "104") (name "DATA13") (class "Default")
      (node (ref "IC17") (pin "14") (pinfunction "6D_14") (pintype "input"))
      (node (ref "IC2") (pin "14") (pinfunction "6D_14") (pintype "input"))
      (node (ref "IC2") (pin "15") (pinfunction "6Q_15") (pintype "tri_state"))
      (node (ref "IC29") (pin "13") (pinfunction "B6_13") (pintype "bidirectional"))
      (node (ref "IC30") (pin "13") (pinfunction "B6_13") (pintype "bidirectional"))
      (node (ref "IC4") (pin "14") (pinfunction "6D_14") (pintype "input"))
      (node (ref "IC4") (pin "15") (pinfunction "6Q_15") (pintype "tri_state"))
      (node (ref "IC6") (pin "14") (pinfunction "6D_14") (pintype "input"))
      (node (ref "IC6") (pin "15") (pinfunction "6Q_15") (pintype "tri_state"))
      (node (ref "IC8") (pin "14") (pinfunction "6D_14") (pintype "input"))
      (node (ref "IC8") (pin "15") (pinfunction "6Q_15") (pintype "tri_state"))
      (node (ref "JP5") (pin "14") (pinfunction "14_14") (pintype "passive"))
      (node (ref "RN4") (pin "7") (pinfunction "1_7") (pintype "passive"))
    )
    (net (code "105") (name "DATA14") (class "Default")
      (node (ref "IC17") (pin "17") (pinfunction "7D_17") (pintype "input"))
      (node (ref "IC2") (pin "16") (pinfunction "7Q_16") (pintype "tri_state"))
      (node (ref "IC2") (pin "17") (pinfunction "7D_17") (pintype "input"))
      (node (ref "IC29") (pin "12") (pinfunction "B7_12") (pintype "bidirectional"))
      (node (ref "IC30") (pin "12") (pinfunction "B7_12") (pintype "bidirectional"))
      (node (ref "IC4") (pin "16") (pinfunction "7Q_16") (pintype "tri_state"))
      (node (ref "IC4") (pin "17") (pinfunction "7D_17") (pintype "input"))
      (node (ref "IC6") (pin "16") (pinfunction "7Q_16") (pintype "tri_state"))
      (node (ref "IC6") (pin "17") (pinfunction "7D_17") (pintype "input"))
      (node (ref "IC8") (pin "16") (pinfunction "7Q_16") (pintype "tri_state"))
      (node (ref "IC8") (pin "17") (pinfunction "7D_17") (pintype "input"))
      (node (ref "JP5") (pin "16") (pinfunction "16_16") (pintype "passive"))
      (node (ref "RN4") (pin "8") (pinfunction "1_8") (pintype "passive"))
    )
    (net (code "106") (name "DATA15") (class "Default")
      (node (ref "IC17") (pin "18") (pinfunction "8D_18") (pintype "input"))
      (node (ref "IC2") (pin "18") (pinfunction "8D_18") (pintype "input"))
      (node (ref "IC2") (pin "19") (pinfunction "8Q_19") (pintype "tri_state"))
      (node (ref "IC29") (pin "11") (pinfunction "B8_11") (pintype "bidirectional"))
      (node (ref "IC30") (pin "11") (pinfunction "B8_11") (pintype "bidirectional"))
      (node (ref "IC4") (pin "18") (pinfunction "8D_18") (pintype "input"))
      (node (ref "IC4") (pin "19") (pinfunction "8Q_19") (pintype "tri_state"))
      (node (ref "IC6") (pin "18") (pinfunction "8D_18") (pintype "input"))
      (node (ref "IC6") (pin "19") (pinfunction "8Q_19") (pintype "tri_state"))
      (node (ref "IC8") (pin "18") (pinfunction "8D_18") (pintype "input"))
      (node (ref "IC8") (pin "19") (pinfunction "8Q_19") (pintype "tri_state"))
      (node (ref "JP5") (pin "18") (pinfunction "18_18") (pintype "passive"))
      (node (ref "RN4") (pin "9") (pinfunction "1_9") (pintype "passive"))
    )
    (net (code "107") (name "GND") (class "Default")
      (node (ref "C1") (pin "2") (pinfunction "2_2") (pintype "passive"))
      (node (ref "C2") (pin "2") (pinfunction "2_2") (pintype "passive"))
      (node (ref "C21") (pin "2") (pinfunction "2_2") (pintype "passive"))
      (node (ref "C22") (pin "2") (pinfunction "2_2") (pintype "passive"))
      (node (ref "C23") (pin "2") (pinfunction "2_2") (pintype "passive"))
      (node (ref "C24") (pin "2") (pinfunction "2_2") (pintype "passive"))
      (node (ref "C25") (pin "2") (pinfunction "2_2") (pintype "passive"))
      (node (ref "C26") (pin "2") (pinfunction "2_2") (pintype "passive"))
      (node (ref "C27") (pin "2") (pinfunction "2_2") (pintype "passive"))
      (node (ref "C28") (pin "2") (pinfunction "2_2") (pintype "passive"))
      (node (ref "C29") (pin "2") (pinfunction "2_2") (pintype "passive"))
      (node (ref "C3") (pin "2") (pinfunction "2_2") (pintype "passive"))
      (node (ref "C30") (pin "2") (pinfunction "2_2") (pintype "passive"))
      (node (ref "C31") (pin "2") (pinfunction "2_2") (pintype "passive"))
      (node (ref "C32") (pin "2") (pinfunction "2_2") (pintype "passive"))
      (node (ref "C33") (pin "2") (pinfunction "2_2") (pintype "passive"))
      (node (ref "C34") (pin "2") (pinfunction "2_2") (pintype "passive"))
      (node (ref "C35") (pin "2") (pinfunction "2_2") (pintype "passive"))
      (node (ref "C36") (pin "2") (pinfunction "2_2") (pintype "passive"))
      (node (ref "C37") (pin "2") (pinfunction "2_2") (pintype "passive"))
      (node (ref "C38") (pin "2") (pinfunction "2_2") (pintype "passive"))
      (node (ref "C39") (pin "2") (pinfunction "2_2") (pintype "passive"))
      (node (ref "C4") (pin "2") (pinfunction "2_2") (pintype "passive"))
      (node (ref "C40") (pin "2") (pinfunction "2_2") (pintype "passive"))
      (node (ref "IC19") (pin "10") (pinfunction "I1_10") (pintype "input"))
      (node (ref "IC19") (pin "9") (pinfunction "I0_9") (pintype "input"))
      (node (ref "IC41") (pin "1") (pinfunction "G_1") (pintype "input"))
      (node (ref "IC41") (pin "10") (pinfunction "GND_10") (pintype "power_in"))
      (node (ref "IC41") (pin "19") (pinfunction "G_19") (pintype "input"))
      (node (ref "JP5") (pin "1") (pinfunction "1_1") (pintype "passive"))
      (node (ref "JP5") (pin "2") (pinfunction "2_2") (pintype "passive"))
      (node (ref "JP5") (pin "27") (pinfunction "27_27") (pintype "passive"))
      (node (ref "JP5") (pin "28") (pinfunction "28_28") (pintype "passive"))
      (node (ref "X1") (pin "A1") (pinfunction "B_A1") (pintype "passive"))
      (node (ref "X1") (pin "A32") (pinfunction "B_A32") (pintype "passive"))
      (node (ref "X1") (pin "B1") (pinfunction "B_B1") (pintype "passive"))
      (node (ref "X1") (pin "B32") (pinfunction "B_B32") (pintype "passive"))
      (node (ref "X1") (pin "C1") (pinfunction "B_C1") (pintype "passive"))
      (node (ref "X1") (pin "C32") (pinfunction "B_C32") (pintype "passive"))
    )
    (net (code "108") (name "HLSWAP") (class "Default")
      (node (ref "IC19") (pin "1") (pinfunction "I0_1") (pintype "input"))
      (node (ref "IC19") (pin "2") (pinfunction "I1_2") (pintype "input"))
      (node (ref "IC20") (pin "13") (pinfunction "I1_13") (pintype "input"))
      (node (ref "X1") (pin "A30") (pinfunction "B_A30") (pintype "passive"))
    )
    (net (code "109") (name "Net-(IC9B-Y0)") (class "Default")
      (node (ref "IC9") (pin "12") (pinfunction "Y0_12") (pintype "output"))
      (node (ref "RD-BRDSEL") (pin "1") (pinfunction "1_1") (pintype "passive"))
    )
    (net (code "110") (name "Net-(IC9B-Y1)") (class "Default")
      (node (ref "IC9") (pin "11") (pinfunction "Y1_11") (pintype "output"))
      (node (ref "RD-BRDSEL") (pin "3") (pinfunction "3_3") (pintype "passive"))
    )
    (net (code "111") (name "Net-(IC9B-Y2)") (class "Default")
      (node (ref "IC9") (pin "10") (pinfunction "Y2_10") (pintype "output"))
      (node (ref "RD-BRDSEL") (pin "5") (pinfunction "5_5") (pintype "passive"))
    )
    (net (code "112") (name "Net-(IC9B-Y3)") (class "Default")
      (node (ref "IC9") (pin "9") (pinfunction "Y3_9") (pintype "output"))
      (node (ref "RD-BRDSEL") (pin "7") (pinfunction "7_7") (pintype "passive"))
    )
    (net (code "113") (name "Net-(IC10A-O)") (class "Default")
      (node (ref "IC1") (pin "1") (pinfunction "OC_1") (pintype "input"))
      (node (ref "IC10") (pin "3") (pinfunction "O_3") (pintype "output"))
    )
    (net (code "114") (name "Net-(IC10B-O)") (class "Default")
      (node (ref "IC10") (pin "6") (pinfunction "O_6") (pintype "output"))
      (node (ref "IC2") (pin "1") (pinfunction "OC_1") (pintype "input"))
    )
    (net (code "115") (name "Net-(IC10C-O)") (class "Default")
      (node (ref "IC10") (pin "8") (pinfunction "O_8") (pintype "output"))
      (node (ref "IC5") (pin "1") (pinfunction "OC_1") (pintype "input"))
    )
    (net (code "116") (name "Net-(IC10D-O)") (class "Default")
      (node (ref "IC10") (pin "11") (pinfunction "O_11") (pintype "output"))
      (node (ref "IC6") (pin "1") (pinfunction "OC_1") (pintype "input"))
    )
    (net (code "117") (name "Net-(IC11B-G)") (class "Default")
      (node (ref "IC11") (pin "15") (pinfunction "G_15") (pintype "input"))
      (node (ref "IC19") (pin "11") (pinfunction "O_11") (pintype "output"))
      (node (ref "IC9") (pin "15") (pinfunction "G_15") (pintype "input"))
    )
    (net (code "118") (name "Net-(IC11B-Y0)") (class "Default")
      (node (ref "IC11") (pin "12") (pinfunction "Y0_12") (pintype "output"))
      (node (ref "WR-BRDSEL") (pin "1") (pinfunction "1_1") (pintype "passive"))
    )
    (net (code "119") (name "Net-(IC11B-Y1)") (class "Default")
      (node (ref "IC11") (pin "11") (pinfunction "Y1_11") (pintype "output"))
      (node (ref "WR-BRDSEL") (pin "3") (pinfunction "3_3") (pintype "passive"))
    )
    (net (code "120") (name "Net-(IC11B-Y2)") (class "Default")
      (node (ref "IC11") (pin "10") (pinfunction "Y2_10") (pintype "output"))
      (node (ref "WR-BRDSEL") (pin "5") (pinfunction "5_5") (pintype "passive"))
    )
    (net (code "121") (name "Net-(IC11B-Y3)") (class "Default")
      (node (ref "IC11") (pin "9") (pinfunction "Y3_9") (pintype "output"))
      (node (ref "WR-BRDSEL") (pin "7") (pinfunction "7_7") (pintype "passive"))
    )
    (net (code "122") (name "Net-(IC13E-O)") (class "Default")
      (node (ref "IC13") (pin "10") (pinfunction "O_10") (pintype "output"))
      (node (ref "IC18") (pin "1") (pinfunction "G_1") (pintype "input"))
    )
    (net (code "123") (name "Net-(IC13F-I)") (class "Default")
      (node (ref "ADDRCLK-SEL") (pin "2") (pinfunction "2_2") (pintype "passive"))
      (node (ref "ADDRCLK-SEL") (pin "4") (pinfunction "4_4") (pintype "passive"))
      (node (ref "ADDRCLK-SEL") (pin "6") (pinfunction "6_6") (pintype "passive"))
      (node (ref "ADDRCLK-SEL") (pin "8") (pinfunction "8_8") (pintype "passive"))
      (node (ref "IC13") (pin "13") (pinfunction "I_13") (pintype "input"))
    )
    (net (code "124") (name "Net-(IC13F-O)") (class "Default")
      (node (ref "IC13") (pin "12") (pinfunction "O_12") (pintype "output"))
      (node (ref "IC16") (pin "11") (pinfunction "CLK_11") (pintype "input"))
      (node (ref "IC17") (pin "11") (pinfunction "CLK_11") (pintype "input"))
    )
    (net (code "125") (name "Net-(IC14A-O)") (class "Default")
      (node (ref "IC14") (pin "3") (pinfunction "O_3") (pintype "output"))
      (node (ref "IC3") (pin "1") (pinfunction "OC_1") (pintype "input"))
    )
    (net (code "126") (name "Net-(IC14B-O)") (class "Default")
      (node (ref "IC14") (pin "6") (pinfunction "O_6") (pintype "output"))
      (node (ref "IC4") (pin "1") (pinfunction "OC_1") (pintype "input"))
    )
    (net (code "127") (name "Net-(IC14C-O)") (class "Default")
      (node (ref "IC14") (pin "8") (pinfunction "O_8") (pintype "output"))
      (node (ref "IC7") (pin "1") (pinfunction "OC_1") (pintype "input"))
    )
    (net (code "128") (name "Net-(IC14D-O)") (class "Default")
      (node (ref "IC14") (pin "11") (pinfunction "O_11") (pintype "output"))
      (node (ref "IC8") (pin "1") (pinfunction "OC_1") (pintype "input"))
    )
    (net (code "129") (name "Net-(IC16A-OC)") (class "Default")
      (node (ref "ADDOUT-SEL") (pin "2") (pinfunction "2_2") (pintype "passive"))
      (node (ref "ADDOUT-SEL") (pin "4") (pinfunction "4_4") (pintype "passive"))
      (node (ref "ADDOUT-SEL") (pin "6") (pinfunction "6_6") (pintype "passive"))
      (node (ref "ADDOUT-SEL") (pin "8") (pinfunction "8_8") (pintype "passive"))
      (node (ref "IC16") (pin "1") (pinfunction "OC_1") (pintype "input"))
      (node (ref "IC17") (pin "1") (pinfunction "OC_1") (pintype "input"))
    )
    (net (code "130") (name "Net-(IC18A-Y0)") (class "Default")
      (node (ref "ADDRCLK-SEL") (pin "1") (pinfunction "1_1") (pintype "passive"))
      (node (ref "IC18") (pin "4") (pinfunction "Y0_4") (pintype "output"))
    )
    (net (code "131") (name "Net-(IC18A-Y1)") (class "Default")
      (node (ref "ADDRCLK-SEL") (pin "3") (pinfunction "3_3") (pintype "passive"))
      (node (ref "IC18") (pin "5") (pinfunction "Y1_5") (pintype "output"))
    )
    (net (code "132") (name "Net-(IC18A-Y2)") (class "Default")
      (node (ref "ADDRCLK-SEL") (pin "5") (pinfunction "5_5") (pintype "passive"))
      (node (ref "IC18") (pin "6") (pinfunction "Y2_6") (pintype "output"))
    )
    (net (code "133") (name "Net-(IC18A-Y3)") (class "Default")
      (node (ref "ADDRCLK-SEL") (pin "7") (pinfunction "7_7") (pintype "passive"))
      (node (ref "IC18") (pin "7") (pinfunction "Y3_7") (pintype "output"))
    )
    (net (code "134") (name "Net-(IC18B-G)") (class "Default")
      (node (ref "IC18") (pin "15") (pinfunction "G_15") (pintype "input"))
      (node (ref "IC19") (pin "6") (pinfunction "O_6") (pintype "output"))
    )
    (net (code "135") (name "Net-(IC18B-Y0)") (class "Default")
      (node (ref "ADDOUT-SEL") (pin "1") (pinfunction "1_1") (pintype "passive"))
      (node (ref "IC18") (pin "12") (pinfunction "Y0_12") (pintype "output"))
    )
    (net (code "136") (name "Net-(IC18B-Y1)") (class "Default")
      (node (ref "ADDOUT-SEL") (pin "3") (pinfunction "3_3") (pintype "passive"))
      (node (ref "IC18") (pin "11") (pinfunction "Y1_11") (pintype "output"))
    )
    (net (code "137") (name "Net-(IC18B-Y2)") (class "Default")
      (node (ref "ADDOUT-SEL") (pin "5") (pinfunction "5_5") (pintype "passive"))
      (node (ref "IC18") (pin "10") (pinfunction "Y2_10") (pintype "output"))
    )
    (net (code "138") (name "Net-(IC18B-Y3)") (class "Default")
      (node (ref "ADDOUT-SEL") (pin "7") (pinfunction "7_7") (pintype "passive"))
      (node (ref "IC18") (pin "9") (pinfunction "Y3_9") (pintype "output"))
    )
    (net (code "139") (name "Net-(IC19A-O)") (class "Default")
      (node (ref "IC19") (pin "3") (pinfunction "O_3") (pintype "output"))
      (node (ref "IC20") (pin "9") (pinfunction "I0_9") (pintype "input"))
    )
    (net (code "140") (name "Net-(IC20A-O)") (class "Default")
      (node (ref "IC20") (pin "10") (pinfunction "I1_10") (pintype "input"))
      (node (ref "IC20") (pin "12") (pinfunction "I0_12") (pintype "input"))
      (node (ref "IC20") (pin "3") (pinfunction "O_3") (pintype "output"))
      (node (ref "IC20") (pin "4") (pinfunction "I0_4") (pintype "input"))
      (node (ref "IC20") (pin "5") (pinfunction "I1_5") (pintype "input"))
    )
    (net (code "141") (name "Net-(IC20B-O)") (class "Default")
      (node (ref "IC20") (pin "6") (pinfunction "O_6") (pintype "output"))
      (node (ref "IC29") (pin "19") (pinfunction "G_19") (pintype "input"))
    )
    (net (code "142") (name "Net-(IC20C-O)") (class "Default")
      (node (ref "IC20") (pin "8") (pinfunction "O_8") (pintype "output"))
      (node (ref "IC31") (pin "19") (pinfunction "G_19") (pintype "input"))
    )
    (net (code "143") (name "Net-(IC20D-O)") (class "Default")
      (node (ref "IC20") (pin "11") (pinfunction "O_11") (pintype "output"))
      (node (ref "IC30") (pin "19") (pinfunction "G_19") (pintype "input"))
    )
    (net (code "144") (name "RA0") (class "Default")
      (node (ref "IC18") (pin "14") (pinfunction "A_14") (pintype "input"))
      (node (ref "IC18") (pin "2") (pinfunction "A_2") (pintype "input"))
      (node (ref "X1") (pin "B6") (pinfunction "B_B6") (pintype "passive"))
    )
    (net (code "145") (name "RA1") (class "Default")
      (node (ref "IC18") (pin "13") (pinfunction "B_13") (pintype "input"))
      (node (ref "IC18") (pin "3") (pinfunction "B_3") (pintype "input"))
      (node (ref "X1") (pin "B5") (pinfunction "B_B5") (pintype "passive"))
    )
    (net (code "146") (name "RACLK") (class "Default")
      (node (ref "IC13") (pin "11") (pinfunction "I_11") (pintype "input"))
      (node (ref "X1") (pin "B4") (pinfunction "B_B4") (pintype "passive"))
    )
    (net (code "147") (name "RAOUT") (class "Default")
      (node (ref "IC19") (pin "4") (pinfunction "I0_4") (pintype "input"))
      (node (ref "IC19") (pin "5") (pinfunction "I1_5") (pintype "input"))
      (node (ref "IC41") (pin "12") (pinfunction "Y4_12") (pintype "tri_state"))
    )
    (net (code "148") (name "RDN") (class "Default")
      (node (ref "IC41") (pin "14") (pinfunction "Y3_14") (pintype "tri_state"))
    )
    (net (code "149") (name "REG-FUNC") (class "Default")
      (node (ref "IC19") (pin "12") (pinfunction "I0_12") (pintype "input"))
      (node (ref "IC19") (pin "13") (pinfunction "I1_13") (pintype "input"))
    )
    (net (code "150") (name "RESET") (class "Default")
      (node (ref "IC41") (pin "18") (pinfunction "Y1_18") (pintype "tri_state"))
    )
    (net (code "151") (name "RRD0") (class "Default")
      (node (ref "IC9") (pin "2") (pinfunction "A_2") (pintype "input"))
      (node (ref "X1") (pin "B12") (pinfunction "B_B12") (pintype "passive"))
    )
    (net (code "152") (name "RRD1") (class "Default")
      (node (ref "IC9") (pin "3") (pinfunction "B_3") (pintype "input"))
      (node (ref "X1") (pin "B13") (pinfunction "B_B13") (pintype "passive"))
    )
    (net (code "153") (name "RRD2") (class "Default")
      (node (ref "IC9") (pin "14") (pinfunction "A_14") (pintype "input"))
      (node (ref "X1") (pin "B14") (pinfunction "B_B14") (pintype "passive"))
    )
    (net (code "154") (name "RRD3") (class "Default")
      (node (ref "IC9") (pin "13") (pinfunction "B_13") (pintype "input"))
      (node (ref "X1") (pin "B15") (pinfunction "B_B15") (pintype "passive"))
    )
    (net (code "155") (name "RRDH") (class "Default")
      (node (ref "IC13") (pin "5") (pinfunction "I_5") (pintype "input"))
      (node (ref "IC41") (pin "7") (pinfunction "Y2_7") (pintype "tri_state"))
    )
    (net (code "156") (name "RRDL") (class "Default")
      (node (ref "IC13") (pin "1") (pinfunction "I_1") (pintype "input"))
      (node (ref "IC41") (pin "3") (pinfunction "Y4_3") (pintype "tri_state"))
    )
    (net (code "157") (name "RUP") (class "Default")
      (node (ref "IC41") (pin "16") (pinfunction "Y2_16") (pintype "tri_state"))
    )
    (net (code "158") (name "RWR0") (class "Default")
      (node (ref "IC11") (pin "2") (pinfunction "A_2") (pintype "input"))
      (node (ref "X1") (pin "B16") (pinfunction "B_B16") (pintype "passive"))
    )
    (net (code "159") (name "RWR1") (class "Default")
      (node (ref "IC11") (pin "3") (pinfunction "B_3") (pintype "input"))
      (node (ref "X1") (pin "B17") (pinfunction "B_B17") (pintype "passive"))
    )
    (net (code "160") (name "RWR2") (class "Default")
      (node (ref "IC11") (pin "14") (pinfunction "A_14") (pintype "input"))
      (node (ref "X1") (pin "B18") (pinfunction "B_B18") (pintype "passive"))
    )
    (net (code "161") (name "RWR3") (class "Default")
      (node (ref "IC11") (pin "13") (pinfunction "B_13") (pintype "input"))
      (node (ref "X1") (pin "B19") (pinfunction "B_B19") (pintype "passive"))
    )
    (net (code "162") (name "RWRH") (class "Default")
      (node (ref "IC13") (pin "9") (pinfunction "I_9") (pintype "input"))
      (node (ref "IC41") (pin "9") (pinfunction "Y1_9") (pintype "tri_state"))
    )
    (net (code "163") (name "RWRL") (class "Default")
      (node (ref "IC13") (pin "3") (pinfunction "I_3") (pintype "input"))
      (node (ref "IC41") (pin "5") (pinfunction "Y3_5") (pintype "tri_state"))
    )
    (net (code "164") (name "VCC") (class "Default")
      (node (ref "C1") (pin "1") (pinfunction "1_1") (pintype "passive"))
      (node (ref "C2") (pin "1") (pinfunction "1_1") (pintype "passive"))
      (node (ref "C21") (pin "1") (pinfunction "1_1") (pintype "passive"))
      (node (ref "C22") (pin "1") (pinfunction "1_1") (pintype "passive"))
      (node (ref "C23") (pin "1") (pinfunction "1_1") (pintype "passive"))
      (node (ref "C24") (pin "1") (pinfunction "1_1") (pintype "passive"))
      (node (ref "C25") (pin "1") (pinfunction "1_1") (pintype "passive"))
      (node (ref "C26") (pin "1") (pinfunction "1_1") (pintype "passive"))
      (node (ref "C27") (pin "1") (pinfunction "1_1") (pintype "passive"))
      (node (ref "C28") (pin "1") (pinfunction "1_1") (pintype "passive"))
      (node (ref "C29") (pin "1") (pinfunction "1_1") (pintype "passive"))
      (node (ref "C3") (pin "1") (pinfunction "1_1") (pintype "passive"))
      (node (ref "C30") (pin "1") (pinfunction "1_1") (pintype "passive"))
      (node (ref "C31") (pin "1") (pinfunction "1_1") (pintype "passive"))
      (node (ref "C32") (pin "1") (pinfunction "1_1") (pintype "passive"))
      (node (ref "C33") (pin "1") (pinfunction "1_1") (pintype "passive"))
      (node (ref "C34") (pin "1") (pinfunction "1_1") (pintype "passive"))
      (node (ref "C35") (pin "1") (pinfunction "1_1") (pintype "passive"))
      (node (ref "C36") (pin "1") (pinfunction "1_1") (pintype "passive"))
      (node (ref "C37") (pin "1") (pinfunction "1_1") (pintype "passive"))
      (node (ref "C38") (pin "1") (pinfunction "1_1") (pintype "passive"))
      (node (ref "C39") (pin "1") (pinfunction "1_1") (pintype "passive"))
      (node (ref "C4") (pin "1") (pinfunction "1_1") (pintype "passive"))
      (node (ref "C40") (pin "1") (pinfunction "1_1") (pintype "passive"))
      (node (ref "IC41") (pin "20") (pinfunction "VCC_20") (pintype "power_in"))
      (node (ref "RN3") (pin "1") (pinfunction "1_1") (pintype "passive"))
      (node (ref "RN4") (pin "1") (pinfunction "1_1") (pintype "passive"))
      (node (ref "X1") (pin "A2") (pinfunction "B_A2") (pintype "passive"))
      (node (ref "X1") (pin "A31") (pinfunction "B_A31") (pintype "passive"))
      (node (ref "X1") (pin "B2") (pinfunction "B_B2") (pintype "passive"))
      (node (ref "X1") (pin "B31") (pinfunction "B_B31") (pintype "passive"))
      (node (ref "X1") (pin "C2") (pinfunction "B_C2") (pintype "passive"))
      (node (ref "X1") (pin "C31") (pinfunction "B_C31") (pintype "passive"))
    )
    (net (code "165") (name "unconnected-(IC19C-O-Pad8)") (class "Default")
      (node (ref "IC19") (pin "8") (pinfunction "O_8") (pintype "output"))
    )
    (net (code "166") (name "unconnected-(X1BJ-B-PadB7)") (class "Default")
      (node (ref "X1") (pin "B7") (pinfunction "B_B7") (pintype "passive"))
    )
    (net (code "167") (name "unconnected-(X1U-B-PadA28)") (class "Default")
      (node (ref "X1") (pin "A28") (pinfunction "B_A28") (pintype "passive"))
    )
  )
)
